# BLOCK_DIAGRAM_TABLE_OF_SHEETS.net
KiCad netlist of a schematic drawn in Altium Designer
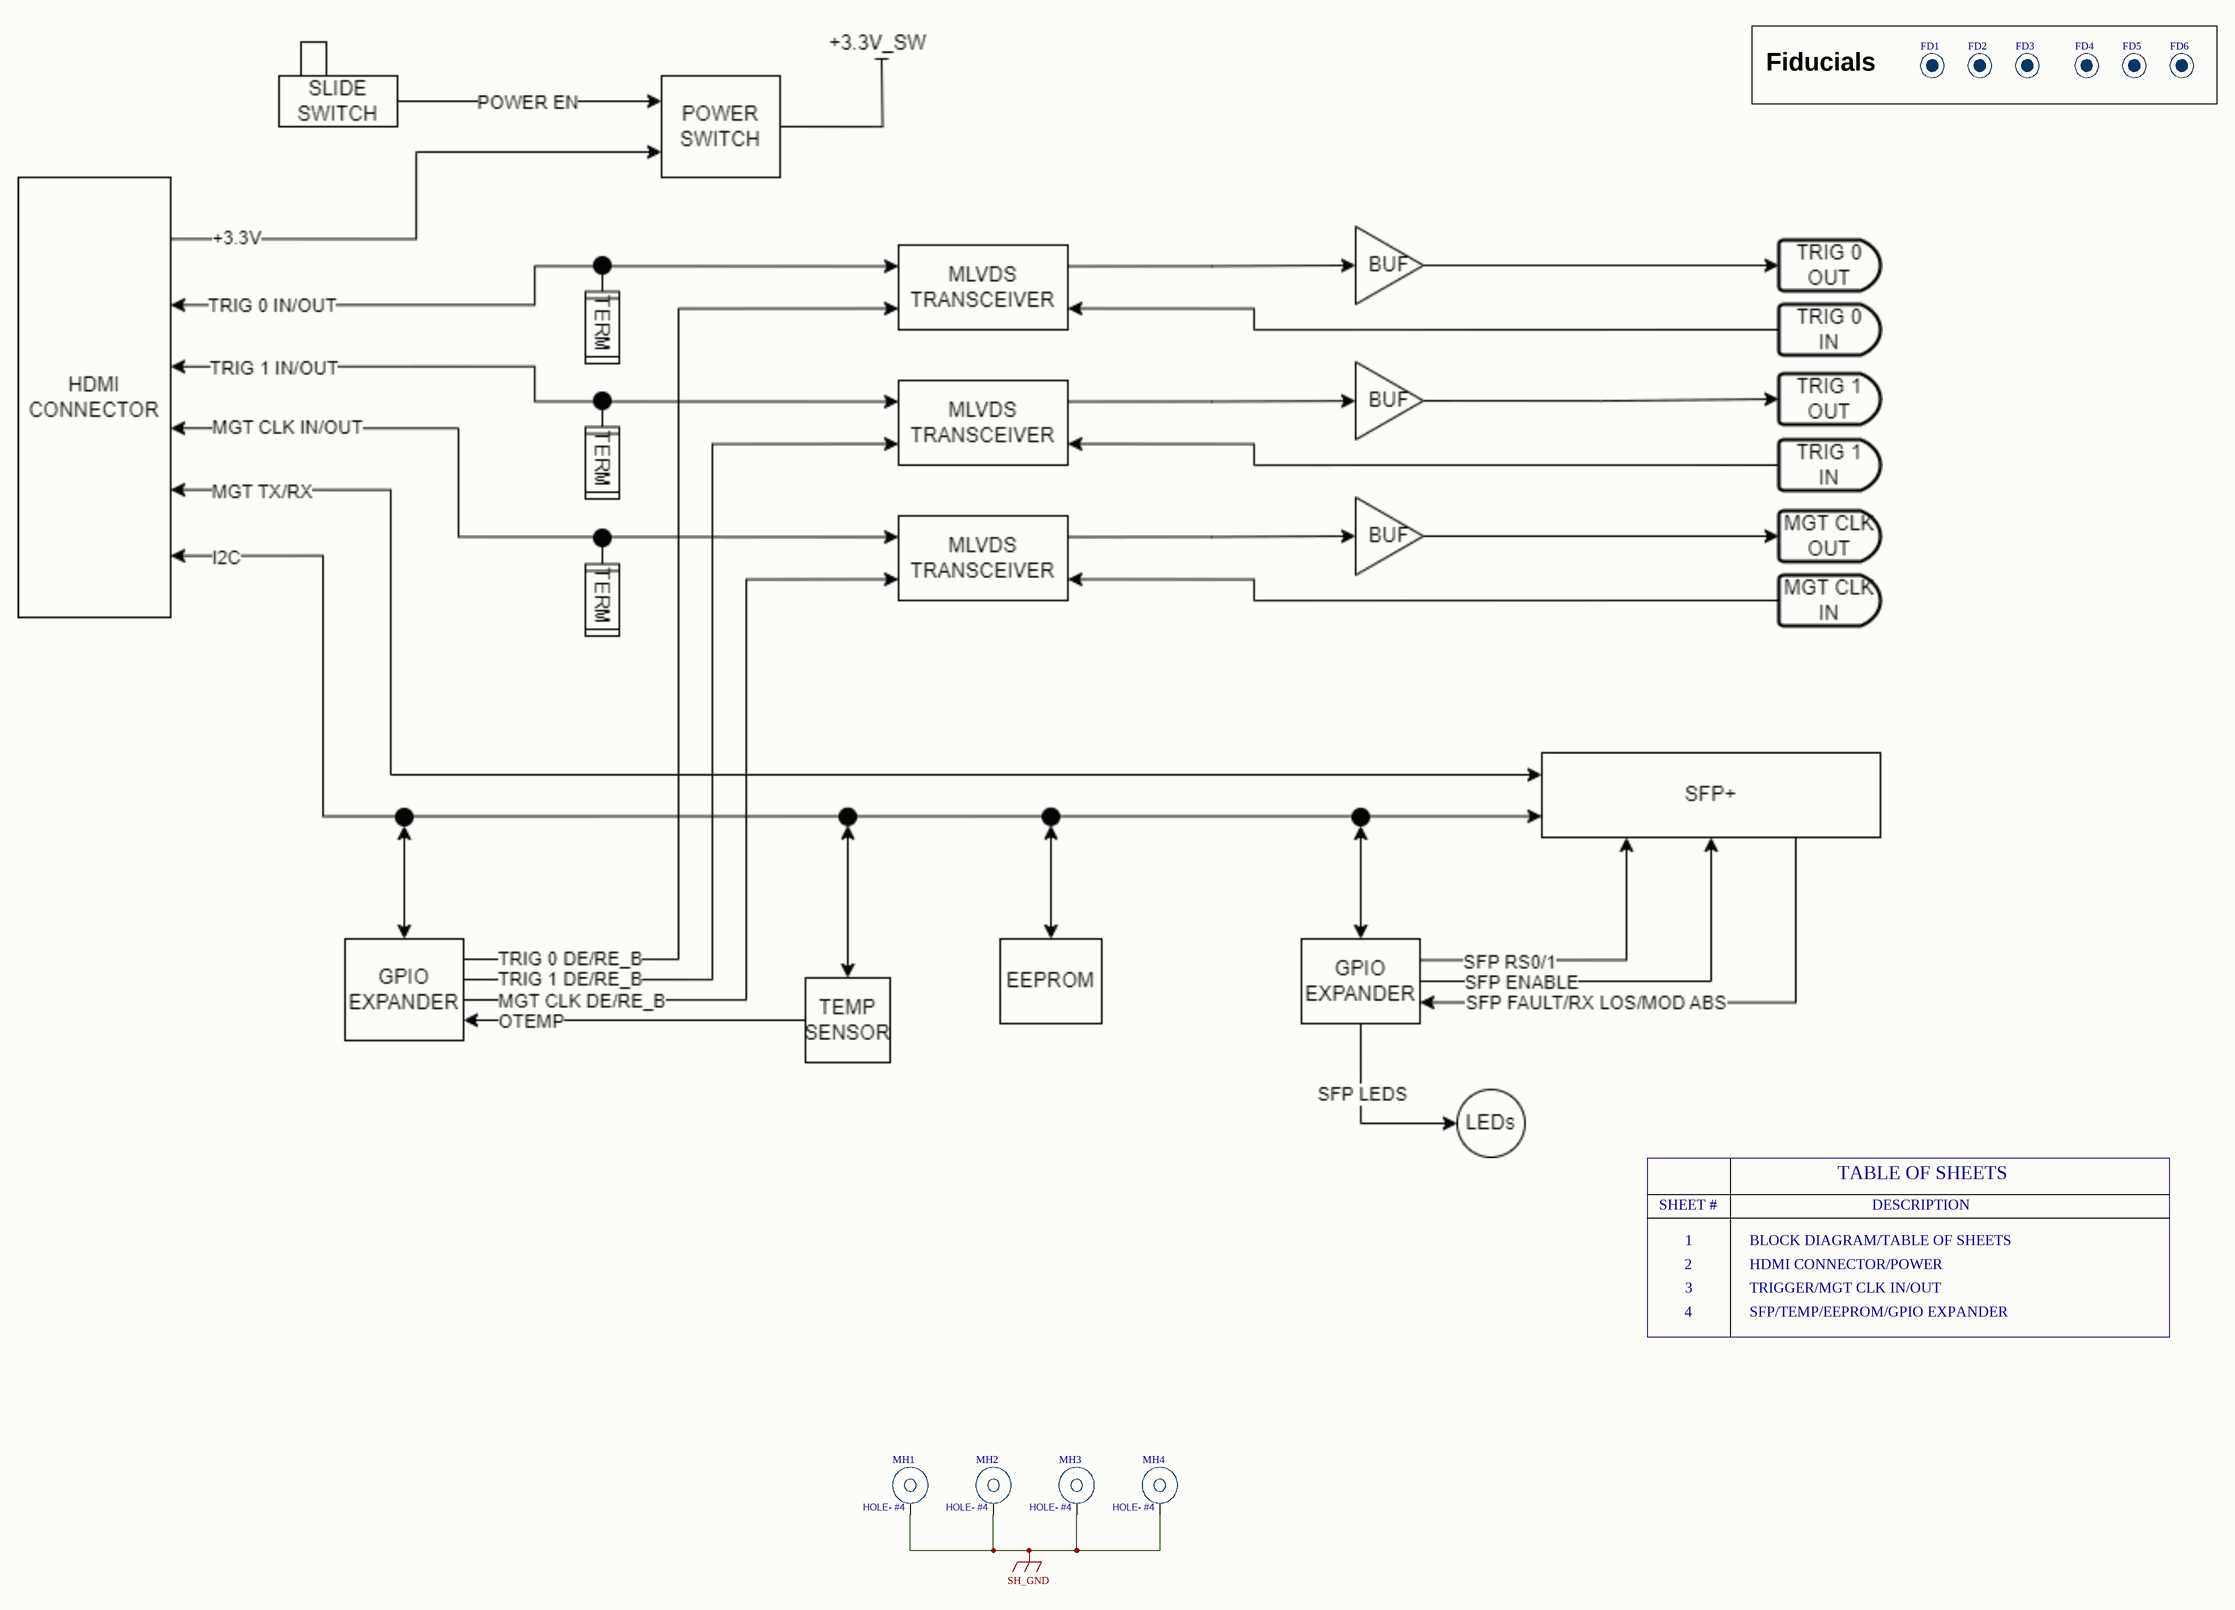
[diagram p0: BLOCK_DIAGRAM_TABLE_OF_SHEETS.SchDoc]

(export (version "E")
  (design (tool "Eeschema 10.0.6"))
  (components
    (comp (ref "FD1")
      (value "FIDUCIAL")
      (footprint "FIDUCIAL-GT")
      (description "Fiducial")
      (fields (field (name "MFG") "PCB FEATURE"))
      (libsource (lib "Atom Computing") (part "FIDUCIAL"))
    )
    (comp (ref "FD2")
      (value "FIDUCIAL")
      (footprint "FIDUCIAL-GT")
      (description "Fiducial")
      (fields (field (name "MFG") "PCB FEATURE"))
      (libsource (lib "Atom Computing") (part "FIDUCIAL"))
    )
    (comp (ref "FD3")
      (value "FIDUCIAL")
      (footprint "FIDUCIAL-GT")
      (description "Fiducial")
      (fields (field (name "MFG") "PCB FEATURE"))
      (libsource (lib "Atom Computing") (part "FIDUCIAL"))
    )
    (comp (ref "FD4")
      (value "FIDUCIAL")
      (footprint "FIDUCIAL-GT")
      (description "Fiducial")
      (fields (field (name "MFG") "PCB FEATURE"))
      (libsource (lib "Atom Computing") (part "FIDUCIAL"))
    )
    (comp (ref "FD5")
      (value "FIDUCIAL")
      (footprint "FIDUCIAL-GT")
      (description "Fiducial")
      (fields (field (name "MFG") "PCB FEATURE"))
      (libsource (lib "Atom Computing") (part "FIDUCIAL"))
    )
    (comp (ref "FD6")
      (value "FIDUCIAL")
      (footprint "FIDUCIAL-GT")
      (description "Fiducial")
      (fields (field (name "MFG") "PCB FEATURE"))
      (libsource (lib "Atom Computing") (part "FIDUCIAL"))
    )
    (comp (ref "MH1")
      (value "HOLE- #4")
      (footprint "HOLE - #4 screw")
      (description "Mounting Hole for #4 screw")
      (fields (field (name "MFG") "NA"))
      (libsource (lib "Atom Computing") (part "HOLE"))
    )
    (comp (ref "MH2")
      (value "HOLE- #4")
      (footprint "HOLE - #4 screw")
      (description "Mounting Hole for #4 screw")
      (fields (field (name "MFG") "NA"))
      (libsource (lib "Atom Computing") (part "HOLE"))
    )
    (comp (ref "MH3")
      (value "HOLE- #4")
      (footprint "HOLE - #4 screw")
      (description "Mounting Hole for #4 screw")
      (fields (field (name "MFG") "NA"))
      (libsource (lib "Atom Computing") (part "HOLE"))
    )
    (comp (ref "MH4")
      (value "HOLE- #4")
      (footprint "HOLE - #4 screw")
      (description "Mounting Hole for #4 screw")
      (fields (field (name "MFG") "NA"))
      (libsource (lib "Atom Computing") (part "HOLE"))
    )
  )
  (nets
    (net (code "1") (name "SH_GND") (class "Default")
      (node (ref "MH1") (pin "1") (pinfunction "GND_1") (pintype "passive"))
      (node (ref "MH2") (pin "1") (pinfunction "GND_1") (pintype "passive"))
      (node (ref "MH3") (pin "1") (pinfunction "GND_1") (pintype "passive"))
      (node (ref "MH4") (pin "1") (pinfunction "GND_1") (pintype "passive"))
    )
  )
)
